# Sheet1.net
KiCad netlist of a schematic drawn in Altium Designer
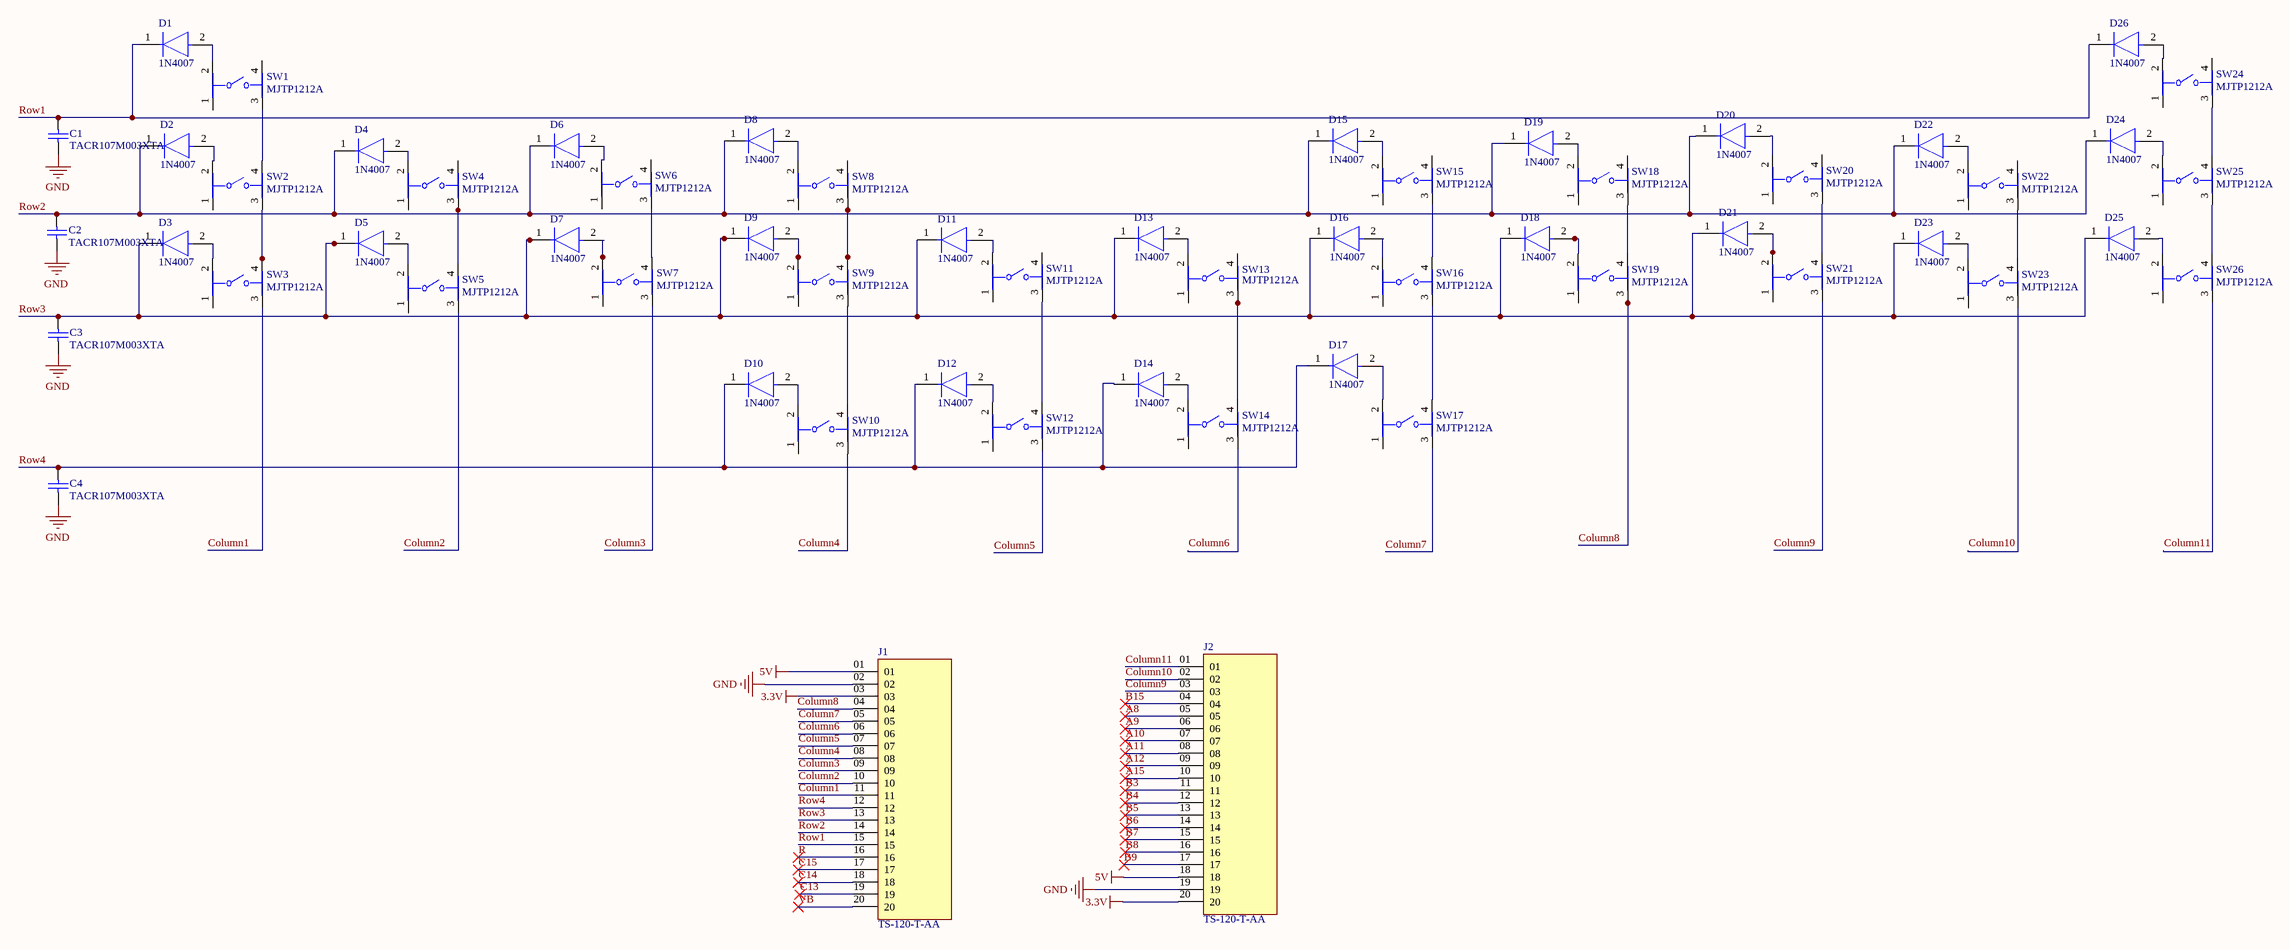
[diagram p0: Sheet1.SchDoc]

(export (version "E")
  (design (tool "Eeschema 10.0.6"))
  (components
    (comp (ref "C1")
      (value "TACR107M003XTA")
      (footprint "CAPC2014X150X70ML20")
      (fields (field (name "MANUFACTURER") "AVX Interconnect / Elco"))
      (libsource (lib "Altium Content Vault") (part "CAP"))
    )
    (comp (ref "C2")
      (value "TACR107M003XTA")
      (footprint "CAPC2014X150X70ML20")
      (fields (field (name "MANUFACTURER") "AVX Interconnect / Elco"))
      (libsource (lib "Altium Content Vault") (part "CAP"))
    )
    (comp (ref "C3")
      (value "TACR107M003XTA")
      (footprint "CAPC2014X150X70ML20")
      (fields (field (name "MANUFACTURER") "AVX Interconnect / Elco"))
      (libsource (lib "Altium Content Vault") (part "CAP"))
    )
    (comp (ref "C4")
      (value "TACR107M003XTA")
      (footprint "CAPC2014X150X70ML20")
      (fields (field (name "MANUFACTURER") "AVX Interconnect / Elco"))
      (libsource (lib "Altium Content Vault") (part "CAP"))
    )
    (comp (ref "D1")
      (value "1N4007")
      (footprint "FP-1N4007-MFG")
      (description "Rectifier diode 1000 V 1 A DO-41, ,")
      (fields
        (field (name "MANUFACTURER") "Diotec")
        (field (name "OCTOPART") "https://octopart.com/1n4007-diotec-4040411")
      )
      (libsource (lib "Altium Content Vault") (part "d7152d700b627762746794eb795d46e"))
    )
    (comp (ref "D2")
      (value "1N4007")
      (footprint "FP-1N4007-MFG")
      (description "Rectifier diode 1000 V 1 A DO-41, ,")
      (fields
        (field (name "MANUFACTURER") "Diotec")
        (field (name "OCTOPART") "https://octopart.com/1n4007-diotec-4040411")
      )
      (libsource (lib "Altium Content Vault") (part "d7152d700b627762746794eb795d46e"))
    )
    (comp (ref "D3")
      (value "1N4007")
      (footprint "FP-1N4007-MFG")
      (description "Rectifier diode 1000 V 1 A DO-41, ,")
      (fields
        (field (name "MANUFACTURER") "Diotec")
        (field (name "OCTOPART") "https://octopart.com/1n4007-diotec-4040411")
      )
      (libsource (lib "Altium Content Vault") (part "d7152d700b627762746794eb795d46e"))
    )
    (comp (ref "D4")
      (value "1N4007")
      (footprint "FP-1N4007-MFG")
      (description "Rectifier diode 1000 V 1 A DO-41, ,")
      (fields
        (field (name "MANUFACTURER") "Diotec")
        (field (name "OCTOPART") "https://octopart.com/1n4007-diotec-4040411")
      )
      (libsource (lib "Altium Content Vault") (part "d7152d700b627762746794eb795d46e"))
    )
    (comp (ref "D5")
      (value "1N4007")
      (footprint "FP-1N4007-MFG")
      (description "Rectifier diode 1000 V 1 A DO-41, ,")
      (fields
        (field (name "MANUFACTURER") "Diotec")
        (field (name "OCTOPART") "https://octopart.com/1n4007-diotec-4040411")
      )
      (libsource (lib "Altium Content Vault") (part "d7152d700b627762746794eb795d46e"))
    )
    (comp (ref "D6")
      (value "1N4007")
      (footprint "FP-1N4007-MFG")
      (description "Rectifier diode 1000 V 1 A DO-41, ,")
      (fields
        (field (name "MANUFACTURER") "Diotec")
        (field (name "OCTOPART") "https://octopart.com/1n4007-diotec-4040411")
      )
      (libsource (lib "Altium Content Vault") (part "d7152d700b627762746794eb795d46e"))
    )
    (comp (ref "D7")
      (value "1N4007")
      (footprint "FP-1N4007-MFG")
      (description "Rectifier diode 1000 V 1 A DO-41, ,")
      (fields
        (field (name "MANUFACTURER") "Diotec")
        (field (name "OCTOPART") "https://octopart.com/1n4007-diotec-4040411")
      )
      (libsource (lib "Altium Content Vault") (part "d7152d700b627762746794eb795d46e"))
    )
    (comp (ref "D8")
      (value "1N4007")
      (footprint "FP-1N4007-MFG")
      (description "Rectifier diode 1000 V 1 A DO-41, ,")
      (fields
        (field (name "MANUFACTURER") "Diotec")
        (field (name "OCTOPART") "https://octopart.com/1n4007-diotec-4040411")
      )
      (libsource (lib "Altium Content Vault") (part "d7152d700b627762746794eb795d46e"))
    )
    (comp (ref "D9")
      (value "1N4007")
      (footprint "FP-1N4007-MFG")
      (description "Rectifier diode 1000 V 1 A DO-41, ,")
      (fields
        (field (name "MANUFACTURER") "Diotec")
        (field (name "OCTOPART") "https://octopart.com/1n4007-diotec-4040411")
      )
      (libsource (lib "Altium Content Vault") (part "d7152d700b627762746794eb795d46e"))
    )
    (comp (ref "D10")
      (value "1N4007")
      (footprint "FP-1N4007-MFG")
      (description "Rectifier diode 1000 V 1 A DO-41, ,")
      (fields
        (field (name "MANUFACTURER") "Diotec")
        (field (name "OCTOPART") "https://octopart.com/1n4007-diotec-4040411")
      )
      (libsource (lib "Altium Content Vault") (part "d7152d700b627762746794eb795d46e"))
    )
    (comp (ref "D11")
      (value "1N4007")
      (footprint "FP-1N4007-MFG")
      (description "Rectifier diode 1000 V 1 A DO-41, ,")
      (fields
        (field (name "MANUFACTURER") "Diotec")
        (field (name "OCTOPART") "https://octopart.com/1n4007-diotec-4040411")
      )
      (libsource (lib "Altium Content Vault") (part "d7152d700b627762746794eb795d46e"))
    )
    (comp (ref "D12")
      (value "1N4007")
      (footprint "FP-1N4007-MFG")
      (description "Rectifier diode 1000 V 1 A DO-41, ,")
      (fields
        (field (name "MANUFACTURER") "Diotec")
        (field (name "OCTOPART") "https://octopart.com/1n4007-diotec-4040411")
      )
      (libsource (lib "Altium Content Vault") (part "d7152d700b627762746794eb795d46e"))
    )
    (comp (ref "D13")
      (value "1N4007")
      (footprint "FP-1N4007-MFG")
      (description "Rectifier diode 1000 V 1 A DO-41, ,")
      (fields
        (field (name "MANUFACTURER") "Diotec")
        (field (name "OCTOPART") "https://octopart.com/1n4007-diotec-4040411")
      )
      (libsource (lib "Altium Content Vault") (part "d7152d700b627762746794eb795d46e"))
    )
    (comp (ref "D14")
      (value "1N4007")
      (footprint "FP-1N4007-MFG")
      (description "Rectifier diode 1000 V 1 A DO-41, ,")
      (fields
        (field (name "MANUFACTURER") "Diotec")
        (field (name "OCTOPART") "https://octopart.com/1n4007-diotec-4040411")
      )
      (libsource (lib "Altium Content Vault") (part "d7152d700b627762746794eb795d46e"))
    )
    (comp (ref "D15")
      (value "1N4007")
      (footprint "FP-1N4007-MFG")
      (description "Rectifier diode 1000 V 1 A DO-41, ,")
      (fields
        (field (name "MANUFACTURER") "Diotec")
        (field (name "OCTOPART") "https://octopart.com/1n4007-diotec-4040411")
      )
      (libsource (lib "Altium Content Vault") (part "d7152d700b627762746794eb795d46e"))
    )
    (comp (ref "D16")
      (value "1N4007")
      (footprint "FP-1N4007-MFG")
      (description "Rectifier diode 1000 V 1 A DO-41, ,")
      (fields
        (field (name "MANUFACTURER") "Diotec")
        (field (name "OCTOPART") "https://octopart.com/1n4007-diotec-4040411")
      )
      (libsource (lib "Altium Content Vault") (part "d7152d700b627762746794eb795d46e"))
    )
    (comp (ref "D17")
      (value "1N4007")
      (footprint "FP-1N4007-MFG")
      (description "Rectifier diode 1000 V 1 A DO-41, ,")
      (fields
        (field (name "MANUFACTURER") "Diotec")
        (field (name "OCTOPART") "https://octopart.com/1n4007-diotec-4040411")
      )
      (libsource (lib "Altium Content Vault") (part "d7152d700b627762746794eb795d46e"))
    )
    (comp (ref "D18")
      (value "1N4007")
      (footprint "FP-1N4007-MFG")
      (description "Rectifier diode 1000 V 1 A DO-41, ,")
      (fields
        (field (name "MANUFACTURER") "Diotec")
        (field (name "OCTOPART") "https://octopart.com/1n4007-diotec-4040411")
      )
      (libsource (lib "Altium Content Vault") (part "d7152d700b627762746794eb795d46e"))
    )
    (comp (ref "D19")
      (value "1N4007")
      (footprint "FP-1N4007-MFG")
      (description "Rectifier diode 1000 V 1 A DO-41, ,")
      (fields
        (field (name "MANUFACTURER") "Diotec")
        (field (name "OCTOPART") "https://octopart.com/1n4007-diotec-4040411")
      )
      (libsource (lib "Altium Content Vault") (part "d7152d700b627762746794eb795d46e"))
    )
    (comp (ref "D20")
      (value "1N4007")
      (footprint "FP-1N4007-MFG")
      (description "Rectifier diode 1000 V 1 A DO-41, ,")
      (fields
        (field (name "MANUFACTURER") "Diotec")
        (field (name "OCTOPART") "https://octopart.com/1n4007-diotec-4040411")
      )
      (libsource (lib "Altium Content Vault") (part "d7152d700b627762746794eb795d46e"))
    )
    (comp (ref "D21")
      (value "1N4007")
      (footprint "FP-1N4007-MFG")
      (description "Rectifier diode 1000 V 1 A DO-41, ,")
      (fields
        (field (name "MANUFACTURER") "Diotec")
        (field (name "OCTOPART") "https://octopart.com/1n4007-diotec-4040411")
      )
      (libsource (lib "Altium Content Vault") (part "d7152d700b627762746794eb795d46e"))
    )
    (comp (ref "D22")
      (value "1N4007")
      (footprint "FP-1N4007-MFG")
      (description "Rectifier diode 1000 V 1 A DO-41, ,")
      (fields
        (field (name "MANUFACTURER") "Diotec")
        (field (name "OCTOPART") "https://octopart.com/1n4007-diotec-4040411")
      )
      (libsource (lib "Altium Content Vault") (part "d7152d700b627762746794eb795d46e"))
    )
    (comp (ref "D23")
      (value "1N4007")
      (footprint "FP-1N4007-MFG")
      (description "Rectifier diode 1000 V 1 A DO-41, ,")
      (fields
        (field (name "MANUFACTURER") "Diotec")
        (field (name "OCTOPART") "https://octopart.com/1n4007-diotec-4040411")
      )
      (libsource (lib "Altium Content Vault") (part "d7152d700b627762746794eb795d46e"))
    )
    (comp (ref "D24")
      (value "1N4007")
      (footprint "FP-1N4007-MFG")
      (description "Rectifier diode 1000 V 1 A DO-41, ,")
      (fields
        (field (name "MANUFACTURER") "Diotec")
        (field (name "OCTOPART") "https://octopart.com/1n4007-diotec-4040411")
      )
      (libsource (lib "Altium Content Vault") (part "d7152d700b627762746794eb795d46e"))
    )
    (comp (ref "D25")
      (value "1N4007")
      (footprint "FP-1N4007-MFG")
      (description "Rectifier diode 1000 V 1 A DO-41, ,")
      (fields
        (field (name "MANUFACTURER") "Diotec")
        (field (name "OCTOPART") "https://octopart.com/1n4007-diotec-4040411")
      )
      (libsource (lib "Altium Content Vault") (part "d7152d700b627762746794eb795d46e"))
    )
    (comp (ref "D26")
      (value "1N4007")
      (footprint "FP-1N4007-MFG")
      (description "Rectifier diode 1000 V 1 A DO-41, ,")
      (fields
        (field (name "MANUFACTURER") "Diotec")
        (field (name "OCTOPART") "https://octopart.com/1n4007-diotec-4040411")
      )
      (libsource (lib "Altium Content Vault") (part "d7152d700b627762746794eb795d46e"))
    )
    (comp (ref "J1")
      (value "TS-120-T-AA")
      (footprint "SAMTEC_TS-120-T-AA")
      (description "Headers & Wire Housings .100 Single Row Screw Machine Terminal Strip")
      (fields (field (name "MF") "Samtec"))
      (libsource (lib "TS-120-T-AA") (part "TS-120-T-AA"))
    )
    (comp (ref "J2")
      (value "TS-120-T-AA")
      (footprint "SAMTEC_TS-120-T-AA")
      (description "Headers & Wire Housings .100 Single Row Screw Machine Terminal Strip")
      (fields (field (name "MF") "Samtec"))
      (libsource (lib "TS-120-T-AA") (part "TS-120-T-AA"))
    )
    (comp (ref "SW1")
      (value "MJTP1212A")
      (footprint "FP-MJTP1212A-MFG")
      (description "SWITCH TACTILE SPST-NO 0.05A 12V")
      (libsource (lib "Altium Content Vault") (part "82b636f13fd696edb7519609c0a8a76"))
    )
    (comp (ref "SW2")
      (value "MJTP1212A")
      (footprint "FP-MJTP1212A-MFG")
      (description "SWITCH TACTILE SPST-NO 0.05A 12V")
      (libsource (lib "Altium Content Vault") (part "82b636f13fd696edb7519609c0a8a76"))
    )
    (comp (ref "SW3")
      (value "MJTP1212A")
      (footprint "FP-MJTP1212A-MFG")
      (description "SWITCH TACTILE SPST-NO 0.05A 12V")
      (libsource (lib "Altium Content Vault") (part "82b636f13fd696edb7519609c0a8a76"))
    )
    (comp (ref "SW4")
      (value "MJTP1212A")
      (footprint "FP-MJTP1212A-MFG")
      (description "SWITCH TACTILE SPST-NO 0.05A 12V")
      (libsource (lib "Altium Content Vault") (part "82b636f13fd696edb7519609c0a8a76"))
    )
    (comp (ref "SW5")
      (value "MJTP1212A")
      (footprint "FP-MJTP1212A-MFG")
      (description "SWITCH TACTILE SPST-NO 0.05A 12V")
      (libsource (lib "Altium Content Vault") (part "82b636f13fd696edb7519609c0a8a76"))
    )
    (comp (ref "SW6")
      (value "MJTP1212A")
      (footprint "FP-MJTP1212A-MFG")
      (description "SWITCH TACTILE SPST-NO 0.05A 12V")
      (libsource (lib "Altium Content Vault") (part "82b636f13fd696edb7519609c0a8a76"))
    )
    (comp (ref "SW7")
      (value "MJTP1212A")
      (footprint "FP-MJTP1212A-MFG")
      (description "SWITCH TACTILE SPST-NO 0.05A 12V")
      (libsource (lib "Altium Content Vault") (part "82b636f13fd696edb7519609c0a8a76"))
    )
    (comp (ref "SW8")
      (value "MJTP1212A")
      (footprint "FP-MJTP1212A-MFG")
      (description "SWITCH TACTILE SPST-NO 0.05A 12V")
      (libsource (lib "Altium Content Vault") (part "82b636f13fd696edb7519609c0a8a76"))
    )
    (comp (ref "SW9")
      (value "MJTP1212A")
      (footprint "FP-MJTP1212A-MFG")
      (description "SWITCH TACTILE SPST-NO 0.05A 12V")
      (libsource (lib "Altium Content Vault") (part "82b636f13fd696edb7519609c0a8a76"))
    )
    (comp (ref "SW10")
      (value "MJTP1212A")
      (footprint "FP-MJTP1212A-MFG")
      (description "SWITCH TACTILE SPST-NO 0.05A 12V")
      (libsource (lib "Altium Content Vault") (part "82b636f13fd696edb7519609c0a8a76"))
    )
    (comp (ref "SW11")
      (value "MJTP1212A")
      (footprint "FP-MJTP1212A-MFG")
      (description "SWITCH TACTILE SPST-NO 0.05A 12V")
      (libsource (lib "Altium Content Vault") (part "82b636f13fd696edb7519609c0a8a76"))
    )
    (comp (ref "SW12")
      (value "MJTP1212A")
      (footprint "FP-MJTP1212A-MFG")
      (description "SWITCH TACTILE SPST-NO 0.05A 12V")
      (libsource (lib "Altium Content Vault") (part "82b636f13fd696edb7519609c0a8a76"))
    )
    (comp (ref "SW13")
      (value "MJTP1212A")
      (footprint "FP-MJTP1212A-MFG")
      (description "SWITCH TACTILE SPST-NO 0.05A 12V")
      (libsource (lib "Altium Content Vault") (part "82b636f13fd696edb7519609c0a8a76"))
    )
    (comp (ref "SW14")
      (value "MJTP1212A")
      (footprint "FP-MJTP1212A-MFG")
      (description "SWITCH TACTILE SPST-NO 0.05A 12V")
      (libsource (lib "Altium Content Vault") (part "82b636f13fd696edb7519609c0a8a76"))
    )
    (comp (ref "SW15")
      (value "MJTP1212A")
      (footprint "FP-MJTP1212A-MFG")
      (description "SWITCH TACTILE SPST-NO 0.05A 12V")
      (libsource (lib "Altium Content Vault") (part "82b636f13fd696edb7519609c0a8a76"))
    )
    (comp (ref "SW16")
      (value "MJTP1212A")
      (footprint "FP-MJTP1212A-MFG")
      (description "SWITCH TACTILE SPST-NO 0.05A 12V")
      (libsource (lib "Altium Content Vault") (part "82b636f13fd696edb7519609c0a8a76"))
    )
    (comp (ref "SW17")
      (value "MJTP1212A")
      (footprint "FP-MJTP1212A-MFG")
      (description "SWITCH TACTILE SPST-NO 0.05A 12V")
      (libsource (lib "Altium Content Vault") (part "82b636f13fd696edb7519609c0a8a76"))
    )
    (comp (ref "SW18")
      (value "MJTP1212A")
      (footprint "FP-MJTP1212A-MFG")
      (description "SWITCH TACTILE SPST-NO 0.05A 12V")
      (libsource (lib "Altium Content Vault") (part "82b636f13fd696edb7519609c0a8a76"))
    )
    (comp (ref "SW19")
      (value "MJTP1212A")
      (footprint "FP-MJTP1212A-MFG")
      (description "SWITCH TACTILE SPST-NO 0.05A 12V")
      (libsource (lib "Altium Content Vault") (part "82b636f13fd696edb7519609c0a8a76"))
    )
    (comp (ref "SW20")
      (value "MJTP1212A")
      (footprint "FP-MJTP1212A-MFG")
      (description "SWITCH TACTILE SPST-NO 0.05A 12V")
      (libsource (lib "Altium Content Vault") (part "82b636f13fd696edb7519609c0a8a76"))
    )
    (comp (ref "SW21")
      (value "MJTP1212A")
      (footprint "FP-MJTP1212A-MFG")
      (description "SWITCH TACTILE SPST-NO 0.05A 12V")
      (libsource (lib "Altium Content Vault") (part "82b636f13fd696edb7519609c0a8a76"))
    )
    (comp (ref "SW22")
      (value "MJTP1212A")
      (footprint "FP-MJTP1212A-MFG")
      (description "SWITCH TACTILE SPST-NO 0.05A 12V")
      (libsource (lib "Altium Content Vault") (part "82b636f13fd696edb7519609c0a8a76"))
    )
    (comp (ref "SW23")
      (value "MJTP1212A")
      (footprint "FP-MJTP1212A-MFG")
      (description "SWITCH TACTILE SPST-NO 0.05A 12V")
      (libsource (lib "Altium Content Vault") (part "82b636f13fd696edb7519609c0a8a76"))
    )
    (comp (ref "SW24")
      (value "MJTP1212A")
      (footprint "FP-MJTP1212A-MFG")
      (description "SWITCH TACTILE SPST-NO 0.05A 12V")
      (libsource (lib "Altium Content Vault") (part "82b636f13fd696edb7519609c0a8a76"))
    )
    (comp (ref "SW25")
      (value "MJTP1212A")
      (footprint "FP-MJTP1212A-MFG")
      (description "SWITCH TACTILE SPST-NO 0.05A 12V")
      (libsource (lib "Altium Content Vault") (part "82b636f13fd696edb7519609c0a8a76"))
    )
    (comp (ref "SW26")
      (value "MJTP1212A")
      (footprint "FP-MJTP1212A-MFG")
      (description "SWITCH TACTILE SPST-NO 0.05A 12V")
      (libsource (lib "Altium Content Vault") (part "82b636f13fd696edb7519609c0a8a76"))
    )
  )
  (nets
    (net (code "1") (name "/A8") (class "Default")
      (node (ref "J2") (pin "05") (pinfunction "05_05") (pintype "passive+no_connect"))
    )
    (net (code "2") (name "/A9") (class "Default")
      (node (ref "J2") (pin "06") (pinfunction "06_06") (pintype "passive+no_connect"))
    )
    (net (code "3") (name "/A10") (class "Default")
      (node (ref "J2") (pin "07") (pinfunction "07_07") (pintype "passive+no_connect"))
    )
    (net (code "4") (name "/A11") (class "Default")
      (node (ref "J2") (pin "08") (pinfunction "08_08") (pintype "passive+no_connect"))
    )
    (net (code "5") (name "/A12") (class "Default")
      (node (ref "J2") (pin "09") (pinfunction "09_09") (pintype "passive+no_connect"))
    )
    (net (code "6") (name "/A15") (class "Default")
      (node (ref "J2") (pin "10") (pinfunction "10_10") (pintype "passive+no_connect"))
    )
    (net (code "7") (name "/B3") (class "Default")
      (node (ref "J2") (pin "11") (pinfunction "11_11") (pintype "passive+no_connect"))
    )
    (net (code "8") (name "/B4") (class "Default")
      (node (ref "J2") (pin "12") (pinfunction "12_12") (pintype "passive+no_connect"))
    )
    (net (code "9") (name "/B5") (class "Default")
      (node (ref "J2") (pin "13") (pinfunction "13_13") (pintype "passive+no_connect"))
    )
    (net (code "10") (name "/B6") (class "Default")
      (node (ref "J2") (pin "14") (pinfunction "14_14") (pintype "passive+no_connect"))
    )
    (net (code "11") (name "/B7") (class "Default")
      (node (ref "J2") (pin "15") (pinfunction "15_15") (pintype "passive+no_connect"))
    )
    (net (code "12") (name "/B8") (class "Default")
      (node (ref "J2") (pin "16") (pinfunction "16_16") (pintype "passive+no_connect"))
    )
    (net (code "13") (name "/B9") (class "Default")
      (node (ref "J2") (pin "17") (pinfunction "17_17") (pintype "passive+no_connect"))
    )
    (net (code "14") (name "/B15") (class "Default")
      (node (ref "J2") (pin "04") (pinfunction "04_04") (pintype "passive+no_connect"))
    )
    (net (code "15") (name "/C13") (class "Default")
      (node (ref "J1") (pin "19") (pinfunction "19_19") (pintype "passive+no_connect"))
    )
    (net (code "16") (name "/C14") (class "Default")
      (node (ref "J1") (pin "18") (pinfunction "18_18") (pintype "passive+no_connect"))
    )
    (net (code "17") (name "/C15") (class "Default")
      (node (ref "J1") (pin "17") (pinfunction "17_17") (pintype "passive+no_connect"))
    )
    (net (code "18") (name "/Column1") (class "Default")
      (node (ref "J1") (pin "11") (pinfunction "11_11") (pintype "passive"))
      (node (ref "SW3") (pin "3") (pinfunction "3_3") (pintype "passive"))
    )
    (net (code "19") (name "/Column2") (class "Default")
      (node (ref "J1") (pin "10") (pinfunction "10_10") (pintype "passive"))
      (node (ref "SW5") (pin "3") (pinfunction "3_3") (pintype "passive"))
    )
    (net (code "20") (name "/Column3") (class "Default")
      (node (ref "J1") (pin "09") (pinfunction "09_09") (pintype "passive"))
      (node (ref "SW7") (pin "3") (pinfunction "3_3") (pintype "passive"))
    )
    (net (code "21") (name "/Column4") (class "Default")
      (node (ref "J1") (pin "08") (pinfunction "08_08") (pintype "passive"))
      (node (ref "SW10") (pin "3") (pinfunction "3_3") (pintype "passive"))
    )
    (net (code "22") (name "/Column5") (class "Default")
      (node (ref "J1") (pin "07") (pinfunction "07_07") (pintype "passive"))
      (node (ref "SW12") (pin "3") (pinfunction "3_3") (pintype "passive"))
    )
    (net (code "23") (name "/Column6") (class "Default")
      (node (ref "J1") (pin "06") (pinfunction "06_06") (pintype "passive"))
      (node (ref "SW14") (pin "3") (pinfunction "3_3") (pintype "passive"))
    )
    (net (code "24") (name "/Column7") (class "Default")
      (node (ref "J1") (pin "05") (pinfunction "05_05") (pintype "passive"))
      (node (ref "SW17") (pin "3") (pinfunction "3_3") (pintype "passive"))
    )
    (net (code "25") (name "/Column8") (class "Default")
      (node (ref "J1") (pin "04") (pinfunction "04_04") (pintype "passive"))
      (node (ref "SW19") (pin "3") (pinfunction "3_3") (pintype "passive"))
    )
    (net (code "26") (name "/Column9") (class "Default")
      (node (ref "J2") (pin "03") (pinfunction "03_03") (pintype "passive"))
      (node (ref "SW21") (pin "3") (pinfunction "3_3") (pintype "passive"))
    )
    (net (code "27") (name "/Column10") (class "Default")
      (node (ref "J2") (pin "02") (pinfunction "02_02") (pintype "passive"))
      (node (ref "SW23") (pin "3") (pinfunction "3_3") (pintype "passive"))
    )
    (net (code "28") (name "/Column11") (class "Default")
      (node (ref "J2") (pin "01") (pinfunction "01_01") (pintype "passive"))
      (node (ref "SW26") (pin "3") (pinfunction "3_3") (pintype "passive"))
    )
    (net (code "29") (name "/R") (class "Default")
      (node (ref "J1") (pin "16") (pinfunction "16_16") (pintype "passive+no_connect"))
    )
    (net (code "30") (name "/Row1") (class "Default")
      (node (ref "C1") (pin "2") (pinfunction "2_2") (pintype "passive"))
      (node (ref "D1") (pin "1") (pinfunction "C_1") (pintype "passive"))
      (node (ref "D26") (pin "1") (pinfunction "C_1") (pintype "passive"))
      (node (ref "J1") (pin "15") (pinfunction "15_15") (pintype "passive"))
    )
    (net (code "31") (name "/Row2") (class "Default")
      (node (ref "C2") (pin "2") (pinfunction "2_2") (pintype "passive"))
      (node (ref "D15") (pin "1") (pinfunction "C_1") (pintype "passive"))
      (node (ref "D19") (pin "1") (pinfunction "C_1") (pintype "passive"))
      (node (ref "D2") (pin "1") (pinfunction "C_1") (pintype "passive"))
      (node (ref "D20") (pin "1") (pinfunction "C_1") (pintype "passive"))
      (node (ref "D22") (pin "1") (pinfunction "C_1") (pintype "passive"))
      (node (ref "D24") (pin "1") (pinfunction "C_1") (pintype "passive"))
      (node (ref "D4") (pin "1") (pinfunction "C_1") (pintype "passive"))
      (node (ref "D6") (pin "1") (pinfunction "C_1") (pintype "passive"))
      (node (ref "D8") (pin "1") (pinfunction "C_1") (pintype "passive"))
      (node (ref "J1") (pin "14") (pinfunction "14_14") (pintype "passive"))
    )
    (net (code "32") (name "/Row3") (class "Default")
      (node (ref "C3") (pin "2") (pinfunction "2_2") (pintype "passive"))
      (node (ref "D11") (pin "1") (pinfunction "C_1") (pintype "passive"))
      (node (ref "D13") (pin "1") (pinfunction "C_1") (pintype "passive"))
      (node (ref "D16") (pin "1") (pinfunction "C_1") (pintype "passive"))
      (node (ref "D18") (pin "1") (pinfunction "C_1") (pintype "passive"))
      (node (ref "D21") (pin "1") (pinfunction "C_1") (pintype "passive"))
      (node (ref "D23") (pin "1") (pinfunction "C_1") (pintype "passive"))
      (node (ref "D25") (pin "1") (pinfunction "C_1") (pintype "passive"))
      (node (ref "D3") (pin "1") (pinfunction "C_1") (pintype "passive"))
      (node (ref "D5") (pin "1") (pinfunction "C_1") (pintype "passive"))
      (node (ref "D7") (pin "1") (pinfunction "C_1") (pintype "passive"))
      (node (ref "D9") (pin "1") (pinfunction "C_1") (pintype "passive"))
      (node (ref "J1") (pin "13") (pinfunction "13_13") (pintype "passive"))
    )
    (net (code "33") (name "/Row4") (class "Default")
      (node (ref "C4") (pin "2") (pinfunction "2_2") (pintype "passive"))
      (node (ref "D10") (pin "1") (pinfunction "C_1") (pintype "passive"))
      (node (ref "D12") (pin "1") (pinfunction "C_1") (pintype "passive"))
      (node (ref "D14") (pin "1") (pinfunction "C_1") (pintype "passive"))
      (node (ref "D17") (pin "1") (pinfunction "C_1") (pintype "passive"))
      (node (ref "J1") (pin "12") (pinfunction "12_12") (pintype "passive"))
    )
    (net (code "34") (name "/VB") (class "Default")
      (node (ref "J1") (pin "20") (pinfunction "20_20") (pintype "passive+no_connect"))
    )
    (net (code "35") (name "3.3V") (class "Default")
      (node (ref "J1") (pin "03") (pinfunction "03_03") (pintype "passive"))
      (node (ref "J2") (pin "20") (pinfunction "20_20") (pintype "passive"))
    )
    (net (code "36") (name "5V") (class "Default")
      (node (ref "J1") (pin "01") (pinfunction "01_01") (pintype "passive"))
      (node (ref "J2") (pin "18") (pinfunction "18_18") (pintype "passive"))
    )
    (net (code "37") (name "GND") (class "Default")
      (node (ref "C1") (pin "1") (pinfunction "1_1") (pintype "passive"))
      (node (ref "C2") (pin "1") (pinfunction "1_1") (pintype "passive"))
      (node (ref "C3") (pin "1") (pinfunction "1_1") (pintype "passive"))
      (node (ref "C4") (pin "1") (pinfunction "1_1") (pintype "passive"))
      (node (ref "J1") (pin "02") (pinfunction "02_02") (pintype "passive"))
      (node (ref "J2") (pin "19") (pinfunction "19_19") (pintype "passive"))
    )
    (net (code "38") (name "Net-(D1-A)") (class "Default")
      (node (ref "D1") (pin "2") (pinfunction "A_2") (pintype "passive"))
      (node (ref "SW1") (pin "2") (pinfunction "2_2") (pintype "passive"))
    )
    (net (code "39") (name "Net-(D2-A)") (class "Default")
      (node (ref "D2") (pin "2") (pinfunction "A_2") (pintype "passive"))
      (node (ref "SW2") (pin "2") (pinfunction "2_2") (pintype "passive"))
    )
    (net (code "40") (name "Net-(D3-A)") (class "Default")
      (node (ref "D3") (pin "2") (pinfunction "A_2") (pintype "passive"))
      (node (ref "SW3") (pin "2") (pinfunction "2_2") (pintype "passive"))
    )
    (net (code "41") (name "Net-(D4-A)") (class "Default")
      (node (ref "D4") (pin "2") (pinfunction "A_2") (pintype "passive"))
      (node (ref "SW4") (pin "2") (pinfunction "2_2") (pintype "passive"))
    )
    (net (code "42") (name "Net-(D5-A)") (class "Default")
      (node (ref "D5") (pin "2") (pinfunction "A_2") (pintype "passive"))
      (node (ref "SW5") (pin "2") (pinfunction "2_2") (pintype "passive"))
    )
    (net (code "43") (name "Net-(D6-A)") (class "Default")
      (node (ref "D6") (pin "2") (pinfunction "A_2") (pintype "passive"))
      (node (ref "SW6") (pin "2") (pinfunction "2_2") (pintype "passive"))
    )
    (net (code "44") (name "Net-(D7-A)") (class "Default")
      (node (ref "D7") (pin "2") (pinfunction "A_2") (pintype "passive"))
      (node (ref "SW7") (pin "2") (pinfunction "2_2") (pintype "passive"))
    )
    (net (code "45") (name "Net-(D8-A)") (class "Default")
      (node (ref "D8") (pin "2") (pinfunction "A_2") (pintype "passive"))
      (node (ref "SW8") (pin "2") (pinfunction "2_2") (pintype "passive"))
    )
    (net (code "46") (name "Net-(D9-A)") (class "Default")
      (node (ref "D9") (pin "2") (pinfunction "A_2") (pintype "passive"))
      (node (ref "SW9") (pin "2") (pinfunction "2_2") (pintype "passive"))
    )
    (net (code "47") (name "Net-(D10-A)") (class "Default")
      (node (ref "D10") (pin "2") (pinfunction "A_2") (pintype "passive"))
      (node (ref "SW10") (pin "2") (pinfunction "2_2") (pintype "passive"))
    )
    (net (code "48") (name "Net-(D11-A)") (class "Default")
      (node (ref "D11") (pin "2") (pinfunction "A_2") (pintype "passive"))
      (node (ref "SW11") (pin "2") (pinfunction "2_2") (pintype "passive"))
    )
    (net (code "49") (name "Net-(D12-A)") (class "Default")
      (node (ref "D12") (pin "2") (pinfunction "A_2") (pintype "passive"))
      (node (ref "SW12") (pin "2") (pinfunction "2_2") (pintype "passive"))
    )
    (net (code "50") (name "Net-(D13-A)") (class "Default")
      (node (ref "D13") (pin "2") (pinfunction "A_2") (pintype "passive"))
      (node (ref "SW13") (pin "2") (pinfunction "2_2") (pintype "passive"))
    )
    (net (code "51") (name "Net-(D14-A)") (class "Default")
      (node (ref "D14") (pin "2") (pinfunction "A_2") (pintype "passive"))
      (node (ref "SW14") (pin "2") (pinfunction "2_2") (pintype "passive"))
    )
    (net (code "52") (name "Net-(D15-A)") (class "Default")
      (node (ref "D15") (pin "2") (pinfunction "A_2") (pintype "passive"))
      (node (ref "SW15") (pin "2") (pinfunction "2_2") (pintype "passive"))
    )
    (net (code "53") (name "Net-(D16-A)") (class "Default")
      (node (ref "D16") (pin "2") (pinfunction "A_2") (pintype "passive"))
      (node (ref "SW16") (pin "2") (pinfunction "2_2") (pintype "passive"))
    )
    (net (code "54") (name "Net-(D17-A)") (class "Default")
      (node (ref "D17") (pin "2") (pinfunction "A_2") (pintype "passive"))
      (node (ref "SW17") (pin "2") (pinfunction "2_2") (pintype "passive"))
    )
    (net (code "55") (name "Net-(D18-A)") (class "Default")
      (node (ref "D18") (pin "2") (pinfunction "A_2") (pintype "passive"))
      (node (ref "SW19") (pin "2") (pinfunction "2_2") (pintype "passive"))
    )
    (net (code "56") (name "Net-(D19-A)") (class "Default")
      (node (ref "D19") (pin "2") (pinfunction "A_2") (pintype "passive"))
      (node (ref "SW18") (pin "2") (pinfunction "2_2") (pintype "passive"))
    )
    (net (code "57") (name "Net-(D20-A)") (class "Default")
      (node (ref "D20") (pin "2") (pinfunction "A_2") (pintype "passive"))
      (node (ref "SW20") (pin "2") (pinfunction "2_2") (pintype "passive"))
    )
    (net (code "58") (name "Net-(D21-A)") (class "Default")
      (node (ref "D21") (pin "2") (pinfunction "A_2") (pintype "passive"))
      (node (ref "SW21") (pin "2") (pinfunction "2_2") (pintype "passive"))
    )
    (net (code "59") (name "Net-(D22-A)") (class "Default")
      (node (ref "D22") (pin "2") (pinfunction "A_2") (pintype "passive"))
      (node (ref "SW22") (pin "2") (pinfunction "2_2") (pintype "passive"))
    )
    (net (code "60") (name "Net-(D23-A)") (class "Default")
      (node (ref "D23") (pin "2") (pinfunction "A_2") (pintype "passive"))
      (node (ref "SW23") (pin "2") (pinfunction "2_2") (pintype "passive"))
    )
    (net (code "61") (name "Net-(D24-A)") (class "Default")
      (node (ref "D24") (pin "2") (pinfunction "A_2") (pintype "passive"))
      (node (ref "SW25") (pin "2") (pinfunction "2_2") (pintype "passive"))
    )
    (net (code "62") (name "Net-(D25-A)") (class "Default")
      (node (ref "D25") (pin "2") (pinfunction "A_2") (pintype "passive"))
      (node (ref "SW26") (pin "2") (pinfunction "2_2") (pintype "passive"))
    )
    (net (code "63") (name "Net-(D26-A)") (class "Default")
      (node (ref "D26") (pin "2") (pinfunction "A_2") (pintype "passive"))
      (node (ref "SW24") (pin "2") (pinfunction "2_2") (pintype "passive"))
    )
    (net (code "64") (name "Net-(SW1-Pad3)") (class "Default")
      (node (ref "SW1") (pin "3") (pinfunction "3_3") (pintype "passive"))
      (node (ref "SW2") (pin "4") (pinfunction "4_4") (pintype "passive"))
    )
    (net (code "65") (name "Net-(SW2-Pad3)") (class "Default")
      (node (ref "SW2") (pin "3") (pinfunction "3_3") (pintype "passive"))
      (node (ref "SW3") (pin "4") (pinfunction "4_4") (pintype "passive"))
    )
    (net (code "66") (name "Net-(SW4-Pad3)") (class "Default")
      (node (ref "SW4") (pin "3") (pinfunction "3_3") (pintype "passive"))
      (node (ref "SW5") (pin "4") (pinfunction "4_4") (pintype "passive"))
    )
    (net (code "67") (name "Net-(SW6-Pad3)") (class "Default")
      (node (ref "SW6") (pin "3") (pinfunction "3_3") (pintype "passive"))
      (node (ref "SW7") (pin "4") (pinfunction "4_4") (pintype "passive"))
    )
    (net (code "68") (name "Net-(SW8-Pad3)") (class "Default")
      (node (ref "SW8") (pin "3") (pinfunction "3_3") (pintype "passive"))
      (node (ref "SW9") (pin "4") (pinfunction "4_4") (pintype "passive"))
    )
    (net (code "69") (name "Net-(SW10-Pad4)") (class "Default")
      (node (ref "SW10") (pin "4") (pinfunction "4_4") (pintype "passive"))
      (node (ref "SW9") (pin "3") (pinfunction "3_3") (pintype "passive"))
    )
    (net (code "70") (name "Net-(SW11-Pad3)") (class "Default")
      (node (ref "SW11") (pin "3") (pinfunction "3_3") (pintype "passive"))
      (node (ref "SW12") (pin "4") (pinfunction "4_4") (pintype "passive"))
    )
    (net (code "71") (name "Net-(SW13-Pad3)") (class "Default")
      (node (ref "SW13") (pin "3") (pinfunction "3_3") (pintype "passive"))
      (node (ref "SW14") (pin "4") (pinfunction "4_4") (pintype "passive"))
    )
    (net (code "72") (name "Net-(SW15-Pad3)") (class "Default")
      (node (ref "SW15") (pin "3") (pinfunction "3_3") (pintype "passive"))
      (node (ref "SW16") (pin "4") (pinfunction "4_4") (pintype "passive"))
    )
    (net (code "73") (name "Net-(SW16-Pad3)") (class "Default")
      (node (ref "SW16") (pin "3") (pinfunction "3_3") (pintype "passive"))
      (node (ref "SW17") (pin "4") (pinfunction "4_4") (pintype "passive"))
    )
    (net (code "74") (name "Net-(SW18-Pad3)") (class "Default")
      (node (ref "SW18") (pin "3") (pinfunction "3_3") (pintype "passive"))
      (node (ref "SW19") (pin "4") (pinfunction "4_4") (pintype "passive"))
    )
    (net (code "75") (name "Net-(SW20-Pad3)") (class "Default")
      (node (ref "SW20") (pin "3") (pinfunction "3_3") (pintype "passive"))
      (node (ref "SW21") (pin "4") (pinfunction "4_4") (pintype "passive"))
    )
    (net (code "76") (name "Net-(SW22-Pad3)") (class "Default")
      (node (ref "SW22") (pin "3") (pinfunction "3_3") (pintype "passive"))
      (node (ref "SW23") (pin "4") (pinfunction "4_4") (pintype "passive"))
    )
    (net (code "77") (name "Net-(SW24-Pad3)") (class "Default")
      (node (ref "SW24") (pin "3") (pinfunction "3_3") (pintype "passive"))
      (node (ref "SW25") (pin "4") (pinfunction "4_4") (pintype "passive"))
    )
    (net (code "78") (name "Net-(SW25-Pad3)") (class "Default")
      (node (ref "SW25") (pin "3") (pinfunction "3_3") (pintype "passive"))
      (node (ref "SW26") (pin "4") (pinfunction "4_4") (pintype "passive"))
    )
    (net (code "79") (name "unconnected-(SW1-Pad1)") (class "Default")
      (node (ref "SW1") (pin "1") (pinfunction "1_1") (pintype "passive"))
    )
    (net (code "80") (name "unconnected-(SW1-Pad4)") (class "Default")
      (node (ref "SW1") (pin "4") (pinfunction "4_4") (pintype "passive"))
    )
    (net (code "81") (name "unconnected-(SW2-Pad1)") (class "Default")
      (node (ref "SW2") (pin "1") (pinfunction "1_1") (pintype "passive"))
    )
    (net (code "82") (name "unconnected-(SW3-Pad1)") (class "Default")
      (node (ref "SW3") (pin "1") (pinfunction "1_1") (pintype "passive"))
    )
    (net (code "83") (name "unconnected-(SW4-Pad1)") (class "Default")
      (node (ref "SW4") (pin "1") (pinfunction "1_1") (pintype "passive"))
    )
    (net (code "84") (name "unconnected-(SW4-Pad4)") (class "Default")
      (node (ref "SW4") (pin "4") (pinfunction "4_4") (pintype "passive"))
    )
    (net (code "85") (name "unconnected-(SW5-Pad1)") (class "Default")
      (node (ref "SW5") (pin "1") (pinfunction "1_1") (pintype "passive"))
    )
    (net (code "86") (name "unconnected-(SW6-Pad1)") (class "Default")
      (node (ref "SW6") (pin "1") (pinfunction "1_1") (pintype "passive"))
    )
    (net (code "87") (name "unconnected-(SW6-Pad4)") (class "Default")
      (node (ref "SW6") (pin "4") (pinfunction "4_4") (pintype "passive"))
    )
    (net (code "88") (name "unconnected-(SW7-Pad1)") (class "Default")
      (node (ref "SW7") (pin "1") (pinfunction "1_1") (pintype "passive"))
    )
    (net (code "89") (name "unconnected-(SW8-Pad1)") (class "Default")
      (node (ref "SW8") (pin "1") (pinfunction "1_1") (pintype "passive"))
    )
    (net (code "90") (name "unconnected-(SW8-Pad4)") (class "Default")
      (node (ref "SW8") (pin "4") (pinfunction "4_4") (pintype "passive"))
    )
    (net (code "91") (name "unconnected-(SW9-Pad1)") (class "Default")
      (node (ref "SW9") (pin "1") (pinfunction "1_1") (pintype "passive"))
    )
    (net (code "92") (name "unconnected-(SW10-Pad1)") (class "Default")
      (node (ref "SW10") (pin "1") (pinfunction "1_1") (pintype "passive"))
    )
    (net (code "93") (name "unconnected-(SW11-Pad1)") (class "Default")
      (node (ref "SW11") (pin "1") (pinfunction "1_1") (pintype "passive"))
    )
    (net (code "94") (name "unconnected-(SW11-Pad4)") (class "Default")
      (node (ref "SW11") (pin "4") (pinfunction "4_4") (pintype "passive"))
    )
    (net (code "95") (name "unconnected-(SW12-Pad1)") (class "Default")
      (node (ref "SW12") (pin "1") (pinfunction "1_1") (pintype "passive"))
    )
    (net (code "96") (name "unconnected-(SW13-Pad1)") (class "Default")
      (node (ref "SW13") (pin "1") (pinfunction "1_1") (pintype "passive"))
    )
    (net (code "97") (name "unconnected-(SW13-Pad4)") (class "Default")
      (node (ref "SW13") (pin "4") (pinfunction "4_4") (pintype "passive"))
    )
    (net (code "98") (name "unconnected-(SW14-Pad1)") (class "Default")
      (node (ref "SW14") (pin "1") (pinfunction "1_1") (pintype "passive"))
    )
    (net (code "99") (name "unconnected-(SW15-Pad1)") (class "Default")
      (node (ref "SW15") (pin "1") (pinfunction "1_1") (pintype "passive"))
    )
    (net (code "100") (name "unconnected-(SW15-Pad4)") (class "Default")
      (node (ref "SW15") (pin "4") (pinfunction "4_4") (pintype "passive"))
    )
    (net (code "101") (name "unconnected-(SW16-Pad1)") (class "Default")
      (node (ref "SW16") (pin "1") (pinfunction "1_1") (pintype "passive"))
    )
    (net (code "102") (name "unconnected-(SW17-Pad1)") (class "Default")
      (node (ref "SW17") (pin "1") (pinfunction "1_1") (pintype "passive"))
    )
    (net (code "103") (name "unconnected-(SW18-Pad1)") (class "Default")
      (node (ref "SW18") (pin "1") (pinfunction "1_1") (pintype "passive"))
    )
    (net (code "104") (name "unconnected-(SW18-Pad4)") (class "Default")
      (node (ref "SW18") (pin "4") (pinfunction "4_4") (pintype "passive"))
    )
    (net (code "105") (name "unconnected-(SW19-Pad1)") (class "Default")
      (node (ref "SW19") (pin "1") (pinfunction "1_1") (pintype "passive"))
    )
    (net (code "106") (name "unconnected-(SW20-Pad1)") (class "Default")
      (node (ref "SW20") (pin "1") (pinfunction "1_1") (pintype "passive"))
    )
    (net (code "107") (name "unconnected-(SW20-Pad4)") (class "Default")
      (node (ref "SW20") (pin "4") (pinfunction "4_4") (pintype "passive"))
    )
    (net (code "108") (name "unconnected-(SW21-Pad1)") (class "Default")
      (node (ref "SW21") (pin "1") (pinfunction "1_1") (pintype "passive"))
    )
    (net (code "109") (name "unconnected-(SW22-Pad1)") (class "Default")
      (node (ref "SW22") (pin "1") (pinfunction "1_1") (pintype "passive"))
    )
    (net (code "110") (name "unconnected-(SW22-Pad4)") (class "Default")
      (node (ref "SW22") (pin "4") (pinfunction "4_4") (pintype "passive"))
    )
    (net (code "111") (name "unconnected-(SW23-Pad1)") (class "Default")
      (node (ref "SW23") (pin "1") (pinfunction "1_1") (pintype "passive"))
    )
    (net (code "112") (name "unconnected-(SW24-Pad1)") (class "Default")
      (node (ref "SW24") (pin "1") (pinfunction "1_1") (pintype "passive"))
    )
    (net (code "113") (name "unconnected-(SW24-Pad4)") (class "Default")
      (node (ref "SW24") (pin "4") (pinfunction "4_4") (pintype "passive"))
    )
    (net (code "114") (name "unconnected-(SW25-Pad1)") (class "Default")
      (node (ref "SW25") (pin "1") (pinfunction "1_1") (pintype "passive"))
    )
    (net (code "115") (name "unconnected-(SW26-Pad1)") (class "Default")
      (node (ref "SW26") (pin "1") (pinfunction "1_1") (pintype "passive"))
    )
  )
)
